# imwiser-basic-v01.net
KiCad netlist of a schematic drawn in EAGLE
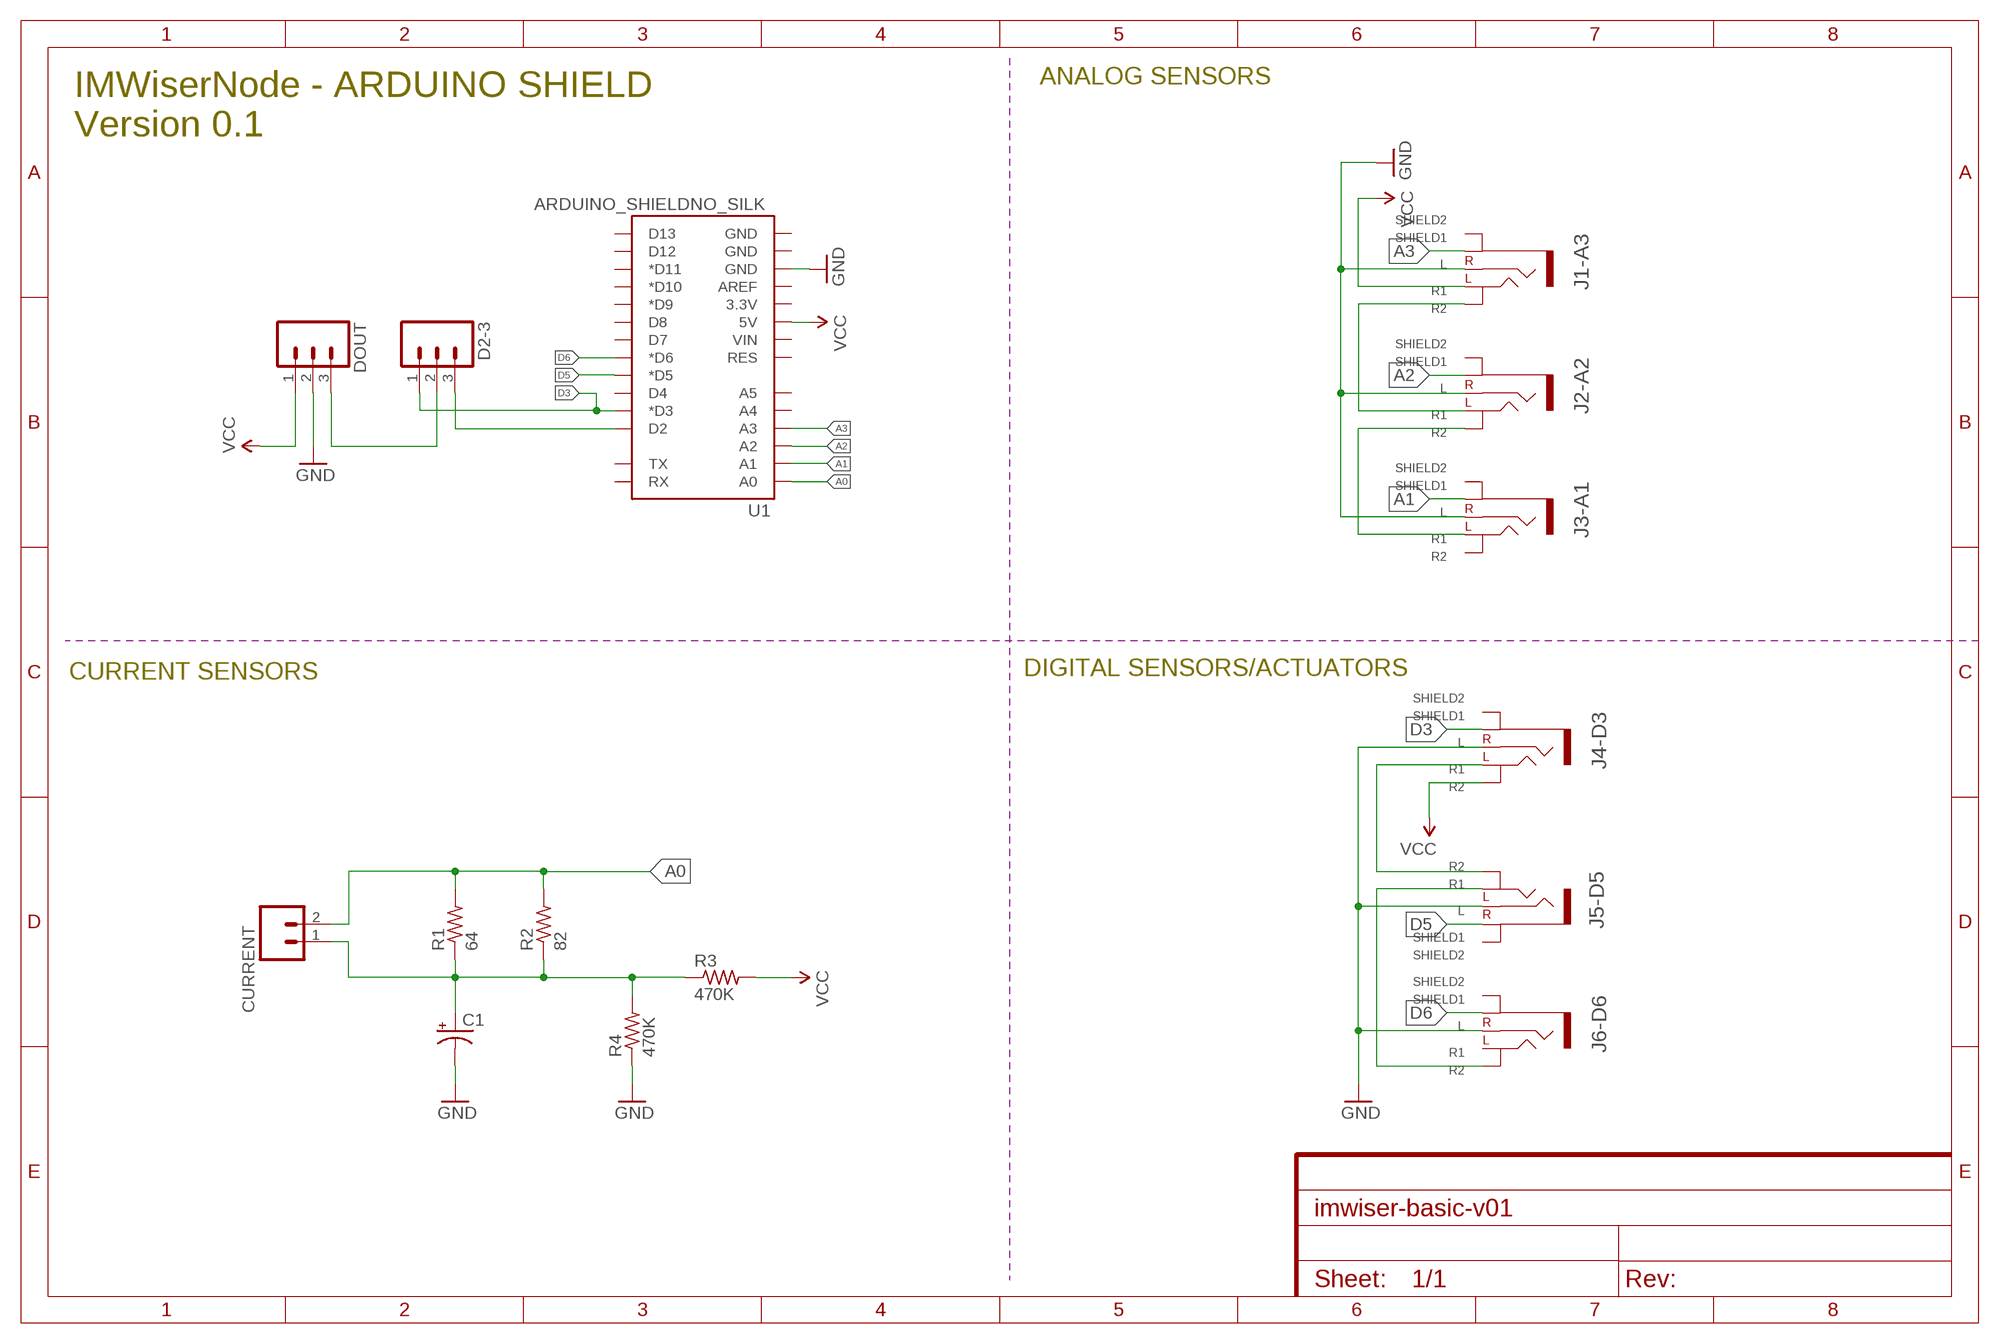
[diagram p0: schematic, sheet 1]

(export (version "E")
  (design (tool "Eeschema 10.0.6"))
  (components
    (comp (ref "C1")
      (value "10UF-25V-20%(PTH)")
      (footprint "eagle-import:CPOL-RADIAL-10UF-25V")
      (libsource (lib "eagle-import") (part "10UF-25V-20%(PTH)"))
    )
    (comp (ref "CURRENT")
      (value "M02PTH")
      (footprint "eagle-import:1X02")
      (libsource (lib "eagle-import") (part "M02PTH"))
    )
    (comp (ref "D2-3")
      (value "M03PTH")
      (footprint "eagle-import:1X03")
      (libsource (lib "eagle-import") (part "M03PTH"))
    )
    (comp (ref "DOUT")
      (value "M03PTH")
      (footprint "eagle-import:1X03")
      (libsource (lib "eagle-import") (part "M03PTH"))
    )
    (comp (ref "J1-A3")
      (value "PJ-313-SPAD")
      (footprint "eagle-import:PJ-313-5PIN-SMALL")
      (libsource (lib "eagle-import") (part "PJ-313-SPAD"))
    )
    (comp (ref "J2-A2")
      (value "PJ-313-SPAD")
      (footprint "eagle-import:PJ-313-5PIN-SMALL")
      (libsource (lib "eagle-import") (part "PJ-313-SPAD"))
    )
    (comp (ref "J3-A1")
      (value "PJ-313-SPAD")
      (footprint "eagle-import:PJ-313-5PIN-SMALL")
      (libsource (lib "eagle-import") (part "PJ-313-SPAD"))
    )
    (comp (ref "J4-D3")
      (value "PJ-313-SPAD")
      (footprint "eagle-import:PJ-313-5PIN-SMALL")
      (libsource (lib "eagle-import") (part "PJ-313-SPAD"))
    )
    (comp (ref "J5-D5")
      (value "PJ-313-SPAD")
      (footprint "eagle-import:PJ-313-5PIN-SMALL")
      (libsource (lib "eagle-import") (part "PJ-313-SPAD"))
    )
    (comp (ref "J6-D6")
      (value "PJ-313-SPAD")
      (footprint "eagle-import:PJ-313-5PIN-SMALL")
      (libsource (lib "eagle-import") (part "PJ-313-SPAD"))
    )
    (comp (ref "R1")
      (value "64")
      (footprint "eagle-import:0207_10")
      (libsource (lib "eagle-import") (part "R-US_0207/10"))
    )
    (comp (ref "R2")
      (value "82")
      (footprint "eagle-import:0207_10")
      (libsource (lib "eagle-import") (part "R-US_0207/10"))
    )
    (comp (ref "R3")
      (value "470K")
      (footprint "eagle-import:0207_10")
      (libsource (lib "eagle-import") (part "R-US_0207/10"))
    )
    (comp (ref "R4")
      (value "470K")
      (footprint "eagle-import:0207_10")
      (libsource (lib "eagle-import") (part "R-US_0207/10"))
    )
    (comp (ref "U1")
      (value "ARDUINO_SHIELDNO_SILK")
      (footprint "eagle-import:DUEMILANOVE_VIAS")
      (libsource (lib "eagle-import") (part "ARDUINO_SHIELDNO_SILK"))
    )
  )
  (nets
    (net (code "1") (name "A0") (class "Default")
      (node (ref "CURRENT") (pin "2") (pinfunction "2_2") (pintype "passive"))
      (node (ref "R1") (pin "2") (pinfunction "2_2") (pintype "passive"))
      (node (ref "R2") (pin "2") (pinfunction "2_2") (pintype "passive"))
      (node (ref "U1") (pin "A0") (pinfunction "A0_A0") (pintype "bidirectional"))
    )
    (net (code "2") (name "A1") (class "Default")
      (node (ref "J3-A1") (pin "1.1") (pinfunction "SHIELD1_1.1") (pintype "bidirectional"))
      (node (ref "U1") (pin "A1") (pinfunction "A1_A1") (pintype "bidirectional"))
    )
    (net (code "3") (name "A2") (class "Default")
      (node (ref "J2-A2") (pin "1.1") (pinfunction "SHIELD1_1.1") (pintype "bidirectional"))
      (node (ref "U1") (pin "A2") (pinfunction "A2_A2") (pintype "bidirectional"))
    )
    (net (code "4") (name "A3") (class "Default")
      (node (ref "J1-A3") (pin "1.1") (pinfunction "SHIELD1_1.1") (pintype "bidirectional"))
      (node (ref "U1") (pin "A3") (pinfunction "A3_A3") (pintype "bidirectional"))
    )
    (net (code "5") (name "D3") (class "Default")
      (node (ref "D2-3") (pin "1") (pinfunction "1_1") (pintype "passive"))
      (node (ref "J4-D3") (pin "1.1") (pinfunction "SHIELD1_1.1") (pintype "bidirectional"))
      (node (ref "U1") (pin "D3") (pinfunction "*D3_D3") (pintype "bidirectional"))
    )
    (net (code "6") (name "D5") (class "Default")
      (node (ref "J5-D5") (pin "1.1") (pinfunction "SHIELD1_1.1") (pintype "bidirectional"))
      (node (ref "U1") (pin "D5") (pinfunction "*D5_D5") (pintype "bidirectional"))
    )
    (net (code "7") (name "D6") (class "Default")
      (node (ref "J6-D6") (pin "1.1") (pinfunction "SHIELD1_1.1") (pintype "bidirectional"))
      (node (ref "U1") (pin "D6") (pinfunction "*D6_D6") (pintype "bidirectional"))
    )
    (net (code "8") (name "GND") (class "Default")
      (node (ref "C1") (pin "2") (pinfunction "-_2") (pintype "passive"))
      (node (ref "DOUT") (pin "2") (pinfunction "2_2") (pintype "passive"))
      (node (ref "J1-A3") (pin "2") (pinfunction "R_2") (pintype "bidirectional"))
      (node (ref "J2-A2") (pin "2") (pinfunction "R_2") (pintype "bidirectional"))
      (node (ref "J3-A1") (pin "2") (pinfunction "R_2") (pintype "bidirectional"))
      (node (ref "J4-D3") (pin "2") (pinfunction "R_2") (pintype "bidirectional"))
      (node (ref "J5-D5") (pin "2") (pinfunction "R_2") (pintype "bidirectional"))
      (node (ref "J6-D6") (pin "2") (pinfunction "R_2") (pintype "bidirectional"))
      (node (ref "R4") (pin "1") (pinfunction "1_1") (pintype "passive"))
      (node (ref "U1") (pin "GND@2") (pinfunction "GND_GND@2") (pintype "bidirectional"))
    )
    (net (code "9") (name "Net-(C1-+)") (class "Default")
      (node (ref "C1") (pin "1") (pinfunction "+_1") (pintype "passive"))
      (node (ref "CURRENT") (pin "1") (pinfunction "1_1") (pintype "passive"))
      (node (ref "R1") (pin "1") (pinfunction "1_1") (pintype "passive"))
      (node (ref "R2") (pin "1") (pinfunction "1_1") (pintype "passive"))
      (node (ref "R3") (pin "1") (pinfunction "1_1") (pintype "passive"))
      (node (ref "R4") (pin "2") (pinfunction "2_2") (pintype "passive"))
    )
    (net (code "10") (name "Net-(D2-3-Pad2)") (class "Default")
      (node (ref "D2-3") (pin "2") (pinfunction "2_2") (pintype "passive"))
      (node (ref "DOUT") (pin "3") (pinfunction "3_3") (pintype "passive"))
    )
    (net (code "11") (name "Net-(D2-3-Pad3)") (class "Default")
      (node (ref "D2-3") (pin "3") (pinfunction "3_3") (pintype "passive"))
      (node (ref "U1") (pin "D2") (pinfunction "D2_D2") (pintype "bidirectional"))
    )
    (net (code "12") (name "Net-(J1-A3-L2)") (class "Default")
      (node (ref "J1-A3") (pin "3.2") (pinfunction "L2_3.2") (pintype "bidirectional"))
      (node (ref "J2-A2") (pin "3.1") (pinfunction "L1_3.1") (pintype "bidirectional"))
    )
    (net (code "13") (name "Net-(J2-A2-L2)") (class "Default")
      (node (ref "J2-A2") (pin "3.2") (pinfunction "L2_3.2") (pintype "bidirectional"))
      (node (ref "J3-A1") (pin "3.1") (pinfunction "L1_3.1") (pintype "bidirectional"))
    )
    (net (code "14") (name "Net-(J4-D3-L1)") (class "Default")
      (node (ref "J4-D3") (pin "3.1") (pinfunction "L1_3.1") (pintype "bidirectional"))
      (node (ref "J5-D5") (pin "3.2") (pinfunction "L2_3.2") (pintype "bidirectional"))
    )
    (net (code "15") (name "Net-(J5-D5-L1)") (class "Default")
      (node (ref "J5-D5") (pin "3.1") (pinfunction "L1_3.1") (pintype "bidirectional"))
      (node (ref "J6-D6") (pin "3.2") (pinfunction "L2_3.2") (pintype "bidirectional"))
    )
    (net (code "16") (name "VCC") (class "Default")
      (node (ref "DOUT") (pin "1") (pinfunction "1_1") (pintype "passive"))
      (node (ref "J1-A3") (pin "3.1") (pinfunction "L1_3.1") (pintype "bidirectional"))
      (node (ref "J4-D3") (pin "3.2") (pinfunction "L2_3.2") (pintype "bidirectional"))
      (node (ref "R3") (pin "2") (pinfunction "2_2") (pintype "passive"))
      (node (ref "U1") (pin "5V") (pinfunction "5V_5V") (pintype "bidirectional"))
    )
    (net (code "17") (name "unconnected-(J1-A3-SHIELD2-Pad1.2)") (class "Default")
      (node (ref "J1-A3") (pin "1.2") (pinfunction "SHIELD2_1.2") (pintype "bidirectional"))
    )
    (net (code "18") (name "unconnected-(J2-A2-SHIELD2-Pad1.2)") (class "Default")
      (node (ref "J2-A2") (pin "1.2") (pinfunction "SHIELD2_1.2") (pintype "bidirectional"))
    )
    (net (code "19") (name "unconnected-(J3-A1-L2-Pad3.2)") (class "Default")
      (node (ref "J3-A1") (pin "3.2") (pinfunction "L2_3.2") (pintype "bidirectional"))
    )
    (net (code "20") (name "unconnected-(J3-A1-SHIELD2-Pad1.2)") (class "Default")
      (node (ref "J3-A1") (pin "1.2") (pinfunction "SHIELD2_1.2") (pintype "bidirectional"))
    )
    (net (code "21") (name "unconnected-(J4-D3-SHIELD2-Pad1.2)") (class "Default")
      (node (ref "J4-D3") (pin "1.2") (pinfunction "SHIELD2_1.2") (pintype "bidirectional"))
    )
    (net (code "22") (name "unconnected-(J5-D5-SHIELD2-Pad1.2)") (class "Default")
      (node (ref "J5-D5") (pin "1.2") (pinfunction "SHIELD2_1.2") (pintype "bidirectional"))
    )
    (net (code "23") (name "unconnected-(J6-D6-L1-Pad3.1)") (class "Default")
      (node (ref "J6-D6") (pin "3.1") (pinfunction "L1_3.1") (pintype "bidirectional"))
    )
    (net (code "24") (name "unconnected-(J6-D6-SHIELD2-Pad1.2)") (class "Default")
      (node (ref "J6-D6") (pin "1.2") (pinfunction "SHIELD2_1.2") (pintype "bidirectional"))
    )
    (net (code "25") (name "unconnected-(U1-*D9-PadD9)") (class "Default")
      (node (ref "U1") (pin "D9") (pinfunction "*D9_D9") (pintype "bidirectional"))
    )
    (net (code "26") (name "unconnected-(U1-*D10-PadD10)") (class "Default")
      (node (ref "U1") (pin "D10") (pinfunction "*D10_D10") (pintype "bidirectional"))
    )
    (net (code "27") (name "unconnected-(U1-*D11-PadD11)") (class "Default")
      (node (ref "U1") (pin "D11") (pinfunction "*D11_D11") (pintype "bidirectional"))
    )
    (net (code "28") (name "unconnected-(U1-GND-PadGND@0)") (class "Default")
      (node (ref "U1") (pin "GND@0") (pinfunction "GND_GND@0") (pintype "bidirectional"))
    )
    (net (code "29") (name "unconnected-(U1-GND-PadGND@1)") (class "Default")
      (node (ref "U1") (pin "GND@1") (pinfunction "GND_GND@1") (pintype "bidirectional"))
    )
    (net (code "30") (name "unconnected-(U1-Pad3.3V)") (class "Default")
      (node (ref "U1") (pin "3.3V") (pinfunction "3.3V_3.3V") (pintype "bidirectional"))
    )
    (net (code "31") (name "unconnected-(U1-PadA4)") (class "Default")
      (node (ref "U1") (pin "A4") (pinfunction "A4_A4") (pintype "bidirectional"))
    )
    (net (code "32") (name "unconnected-(U1-PadA5)") (class "Default")
      (node (ref "U1") (pin "A5") (pinfunction "A5_A5") (pintype "bidirectional"))
    )
    (net (code "33") (name "unconnected-(U1-PadAREF)") (class "Default")
      (node (ref "U1") (pin "AREF") (pinfunction "AREF_AREF") (pintype "bidirectional"))
    )
    (net (code "34") (name "unconnected-(U1-PadD4)") (class "Default")
      (node (ref "U1") (pin "D4") (pinfunction "D4_D4") (pintype "bidirectional"))
    )
    (net (code "35") (name "unconnected-(U1-PadD7)") (class "Default")
      (node (ref "U1") (pin "D7") (pinfunction "D7_D7") (pintype "bidirectional"))
    )
    (net (code "36") (name "unconnected-(U1-PadD8)") (class "Default")
      (node (ref "U1") (pin "D8") (pinfunction "D8_D8") (pintype "bidirectional"))
    )
    (net (code "37") (name "unconnected-(U1-PadD12)") (class "Default")
      (node (ref "U1") (pin "D12") (pinfunction "D12_D12") (pintype "bidirectional"))
    )
    (net (code "38") (name "unconnected-(U1-PadD13)") (class "Default")
      (node (ref "U1") (pin "D13") (pinfunction "D13_D13") (pintype "bidirectional"))
    )
    (net (code "39") (name "unconnected-(U1-PadRES)") (class "Default")
      (node (ref "U1") (pin "RES") (pinfunction "RES_RES") (pintype "bidirectional"))
    )
    (net (code "40") (name "unconnected-(U1-PadRX)") (class "Default")
      (node (ref "U1") (pin "RX") (pinfunction "RX_RX") (pintype "bidirectional"))
    )
    (net (code "41") (name "unconnected-(U1-PadTX)") (class "Default")
      (node (ref "U1") (pin "TX") (pinfunction "TX_TX") (pintype "bidirectional"))
    )
    (net (code "42") (name "unconnected-(U1-PadVIN)") (class "Default")
      (node (ref "U1") (pin "VIN") (pinfunction "VIN_VIN") (pintype "bidirectional"))
    )
  )
)
